# Schema_Circuit_PIA.net
KiCad netlist of a schematic drawn in EasyEDA Pro
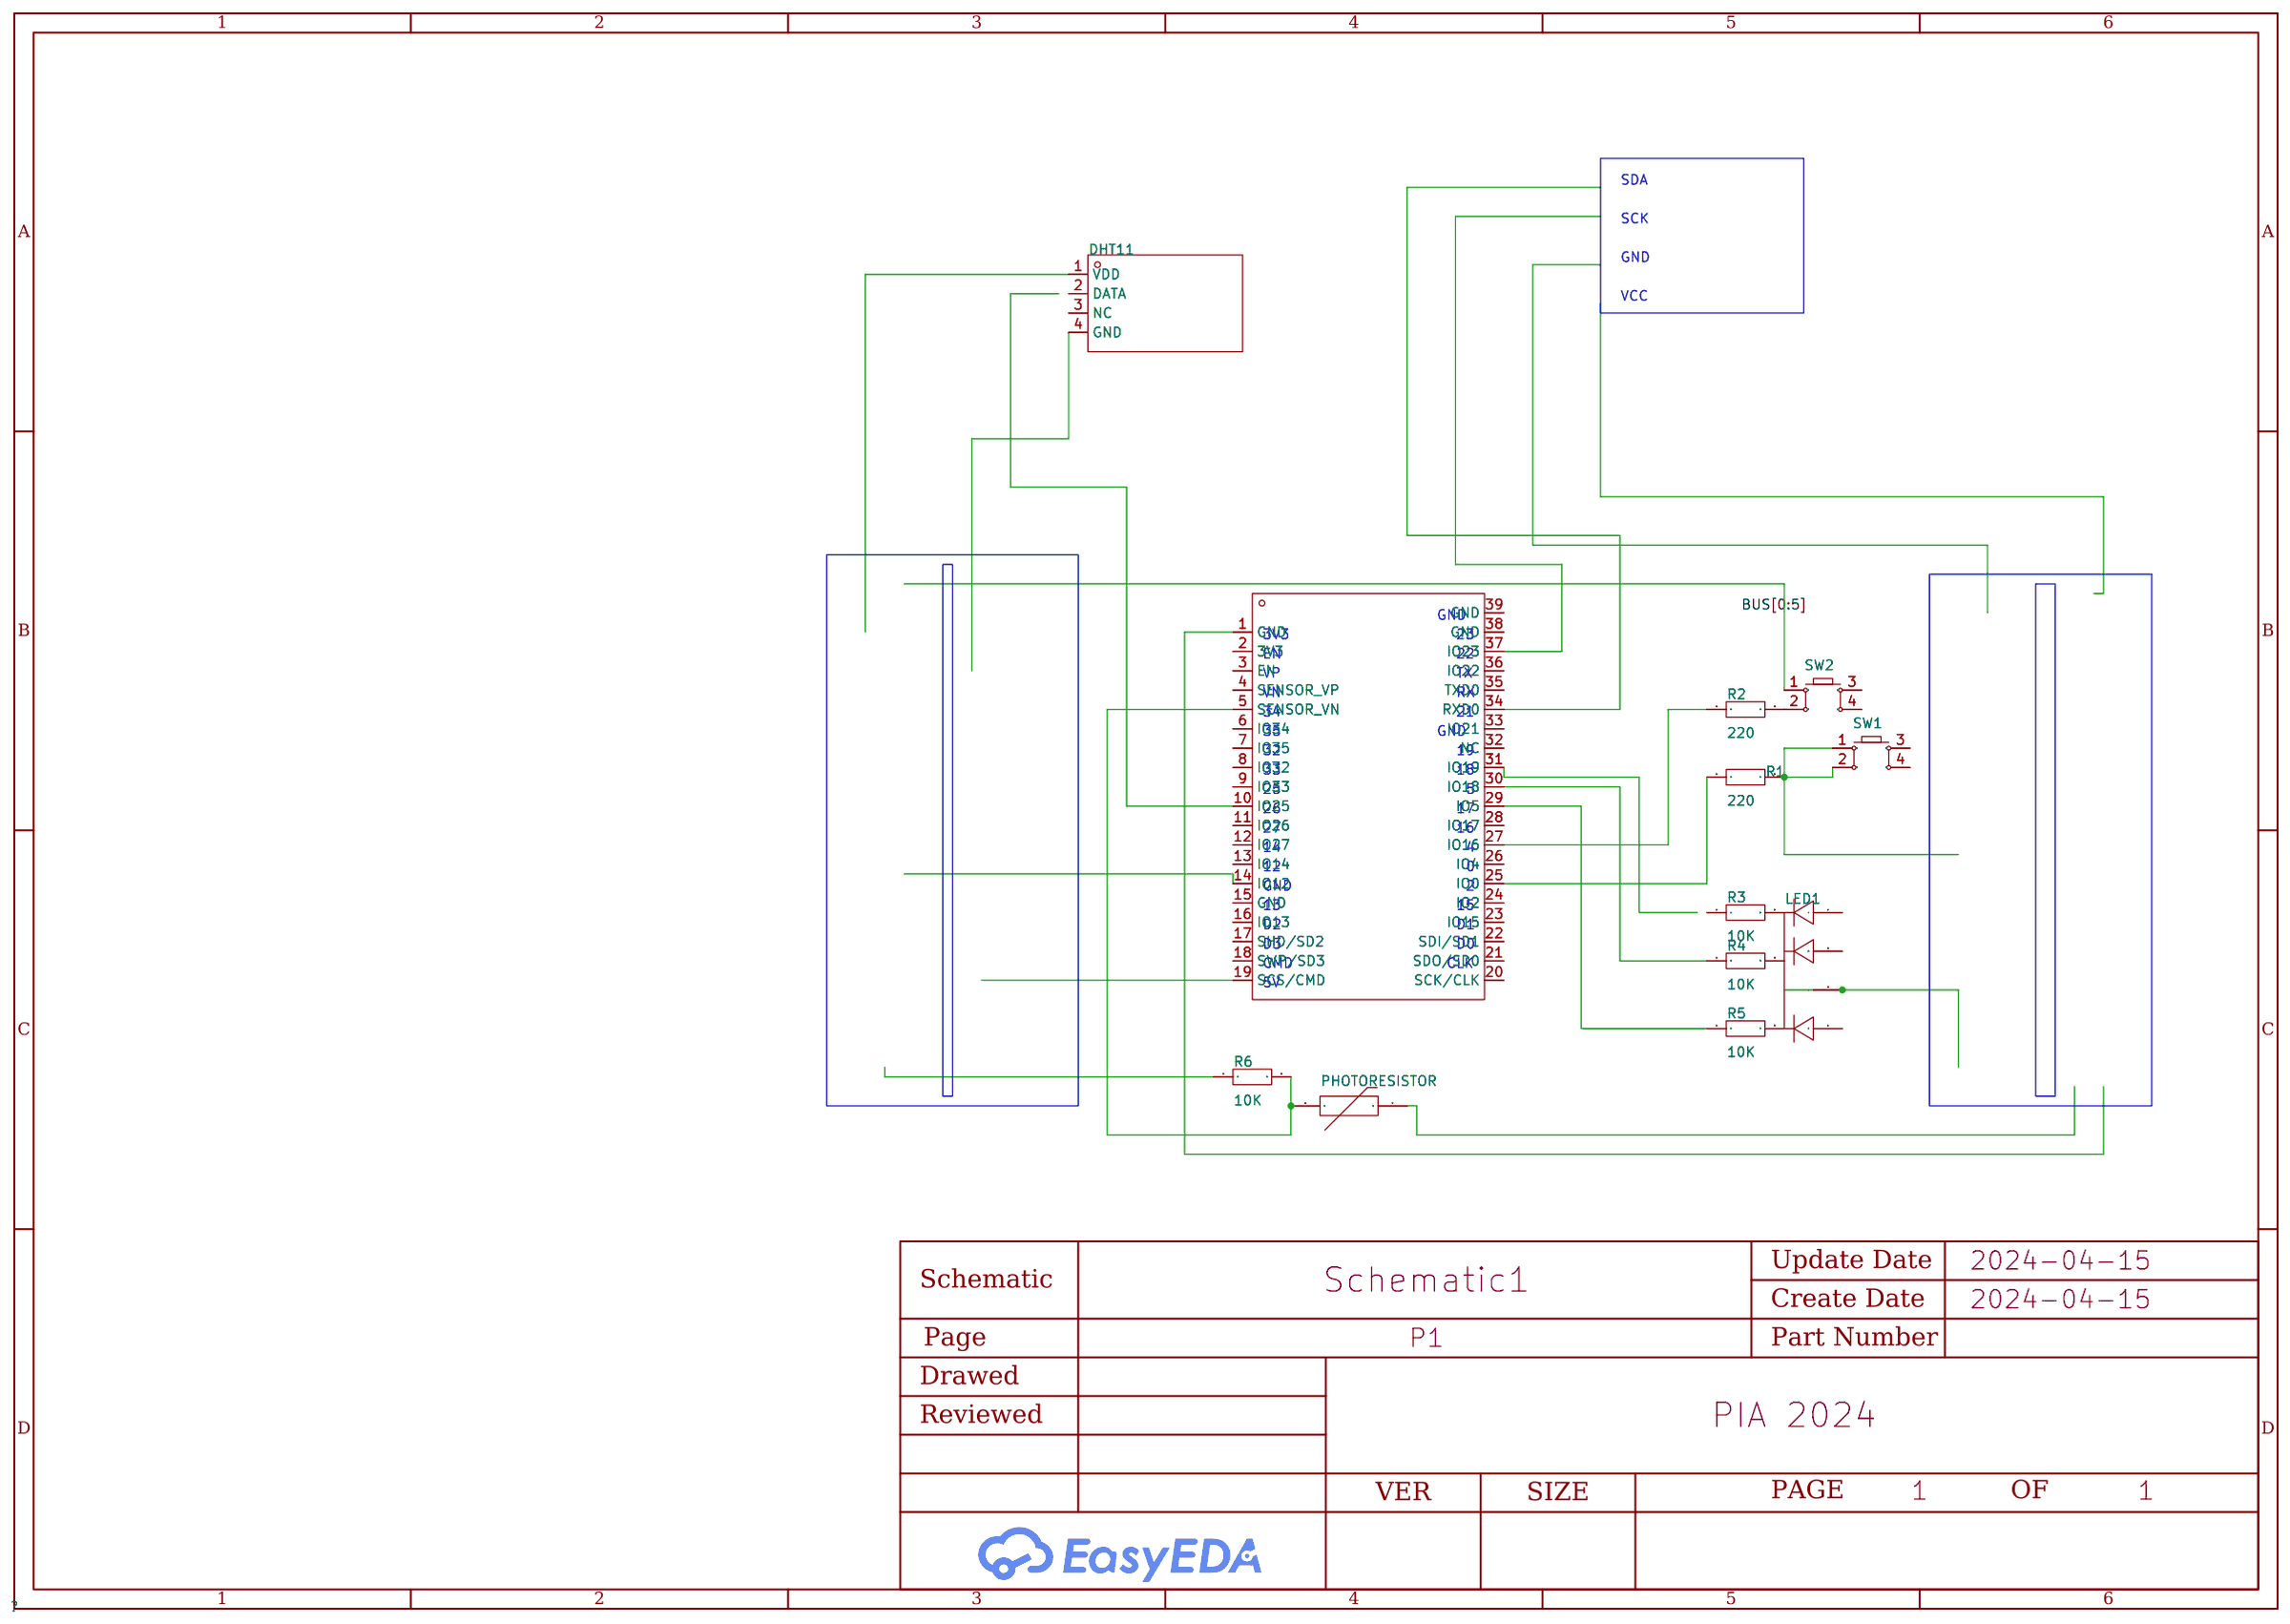
[diagram p0: schematic sheet]

(export (version "E")
  (design (tool "Eeschema 10.0.6"))
  (components
    (comp (ref "DHT11")
      (value "~")
      (footprint "easyedapro:SENSOR-TH_DHT11")
      (fields (field (name "Manufacturer Part") "DHT11") (field (name "Manufacturer") "广州奥松"))
      (libsource (lib "easyedapro") (part "DHT11"))
    )
    (comp (ref "LED1")
      (value "~")
      (footprint "easyedapro:LED-TH_4P-BD5.8-P1.30")
      (description "Emitted Color:RGB")
      (fields
        (field (name "Manufacturer Part") "TJ-L5FYTXHMCSLCRGB-A5")
        (field (name "Manufacturer") "TOGIALED(台湾统佳)")
      )
      (libsource (lib "easyedapro") (part "TJ-L5FYTXHMCSLCRGB-A5"))
    )
    (comp (ref "PHOTORESISTOR")
      (value "~")
      (footprint "easyedapro:RES-TH_L17.5-W6.0-P7.50-D0.8-S5.20")
      (fields (field (name "Manufacturer Part") "MF72 5D15") (field (name "Manufacturer") "时恒"))
      (libsource (lib "easyedapro") (part "MF72-5D15"))
    )
    (comp (ref "R1") (value "220") (footprint "easyedapro:R0603") (libsource (lib "easyedapro") (part "电阻")))
    (comp (ref "R2") (value "220") (footprint "easyedapro:R0603") (libsource (lib "easyedapro") (part "电阻")))
    (comp (ref "R3") (value "10K") (footprint "easyedapro:R0603") (libsource (lib "easyedapro") (part "电阻")))
    (comp (ref "R4") (value "10K") (footprint "easyedapro:R0603") (libsource (lib "easyedapro") (part "电阻")))
    (comp (ref "R5") (value "10K") (footprint "easyedapro:R0603") (libsource (lib "easyedapro") (part "电阻")))
    (comp (ref "R6") (value "10K") (footprint "easyedapro:R0603") (libsource (lib "easyedapro") (part "电阻")))
    (comp (ref "SW1")
      (value "~")
      (footprint "easyedapro:KEY-TH_4P-L6.0-W6.0-P3.90-LS6.5")
      (libsource (lib "easyedapro") (part "轻触按键"))
    )
    (comp (ref "SW2")
      (value "~")
      (footprint "easyedapro:KEY-TH_4P-L6.0-W6.0-P3.90-LS6.5")
      (libsource (lib "easyedapro") (part "轻触按键"))
    )
    (comp (ref "U1")
      (value "~")
      (footprint "easyedapro:WIFIM-SMD_ESP-32S")
      (fields
        (field (name "Manufacturer Part") "ESP32-WROOM-32")
        (field (name "Manufacturer") "ESPRESSIF(乐鑫)")
      )
      (libsource (lib "easyedapro") (part "ESP32-WROOM-32"))
    )
  )
  (nets
    (net (code "2") (name "Net-(R1-Pad2)") (class "Default")
      (node (ref "R1") (pin "2") (pinfunction "2_2") (pintype "input"))
      (node (ref "SW1") (pin "1") (pinfunction "1_1") (pintype "input"))
      (node (ref "SW1") (pin "2") (pinfunction "2_2") (pintype "input"))
    )
    (net (code "3") (name "Net-(R2-Pad2)") (class "Default")
      (node (ref "R2") (pin "2") (pinfunction "2_2") (pintype "input"))
      (node (ref "SW2") (pin "2") (pinfunction "2_2") (pintype "input"))
    )
    (net (code "4") (name "Net-(U1-IO0)") (class "Default")
      (node (ref "R1") (pin "1") (pinfunction "1_1") (pintype "input"))
      (node (ref "U1") (pin "25") (pinfunction "IO0_25") (pintype "input"))
    )
    (net (code "5") (name "Net-(U1-IO5)") (class "Default")
      (node (ref "R5") (pin "1") (pinfunction "1_1") (pintype "input"))
      (node (ref "U1") (pin "29") (pinfunction "IO5_29") (pintype "input"))
    )
    (net (code "6") (name "Net-(U1-IO16)") (class "Default")
      (node (ref "R2") (pin "1") (pinfunction "1_1") (pintype "input"))
      (node (ref "U1") (pin "27") (pinfunction "IO16_27") (pintype "input"))
    )
    (net (code "7") (name "Net-(U1-IO18)") (class "Default")
      (node (ref "R4") (pin "1") (pinfunction "1_1") (pintype "input"))
      (node (ref "U1") (pin "30") (pinfunction "IO18_30") (pintype "input"))
    )
    (net (code "8") (name "Net-(U1-SENSOR_VN)") (class "Default")
      (node (ref "PHOTORESISTOR") (pin "2") (pinfunction "2_2") (pintype "input"))
      (node (ref "R6") (pin "2") (pinfunction "2_2") (pintype "input"))
      (node (ref "U1") (pin "5") (pinfunction "SENSOR_VN_5") (pintype "input"))
    )
    (net (code "9") (name "unconnected-(DHT11-DATA-Pad2)") (class "Default")
      (node (ref "DHT11") (pin "2") (pinfunction "DATA_2") (pintype "input"))
    )
    (net (code "10") (name "unconnected-(DHT11-GND-Pad4)") (class "Default")
      (node (ref "DHT11") (pin "4") (pinfunction "GND_4") (pintype "input"))
    )
    (net (code "11") (name "unconnected-(DHT11-NC-Pad3)") (class "Default")
      (node (ref "DHT11") (pin "3") (pinfunction "NC_3") (pintype "input"))
    )
    (net (code "12") (name "unconnected-(DHT11-VDD-Pad1)") (class "Default")
      (node (ref "DHT11") (pin "1") (pinfunction "VDD_1") (pintype "input"))
    )
    (net (code "13") (name "unconnected-(LED1---Pad2)") (class "Default")
      (node (ref "LED1") (pin "2") (pinfunction "-_2") (pintype "input"))
    )
    (net (code "14") (name "unconnected-(LED1-Pad1)") (class "Default")
      (node (ref "LED1") (pin "1") (pinfunction "1_1") (pintype "input"))
    )
    (net (code "15") (name "unconnected-(LED1-Pad3)") (class "Default")
      (node (ref "LED1") (pin "3") (pinfunction "3_3") (pintype "input"))
    )
    (net (code "16") (name "unconnected-(LED1-Pad4)") (class "Default")
      (node (ref "LED1") (pin "4") (pinfunction "4_4") (pintype "input"))
    )
    (net (code "17") (name "unconnected-(PHOTORESISTOR-Pad1)") (class "Default")
      (node (ref "PHOTORESISTOR") (pin "1") (pinfunction "1_1") (pintype "input"))
    )
    (net (code "18") (name "unconnected-(R3-Pad1)") (class "Default")
      (node (ref "R3") (pin "1") (pinfunction "1_1") (pintype "input"))
    )
    (net (code "19") (name "unconnected-(R3-Pad2)") (class "Default")
      (node (ref "R3") (pin "2") (pinfunction "2_2") (pintype "input"))
    )
    (net (code "20") (name "unconnected-(R4-Pad2)") (class "Default")
      (node (ref "R4") (pin "2") (pinfunction "2_2") (pintype "input"))
    )
    (net (code "21") (name "unconnected-(R5-Pad2)") (class "Default")
      (node (ref "R5") (pin "2") (pinfunction "2_2") (pintype "input"))
    )
    (net (code "22") (name "unconnected-(R6-Pad1)") (class "Default")
      (node (ref "R6") (pin "1") (pinfunction "1_1") (pintype "input"))
    )
    (net (code "23") (name "unconnected-(SW1-Pad3)") (class "Default")
      (node (ref "SW1") (pin "3") (pinfunction "3_3") (pintype "input"))
    )
    (net (code "24") (name "unconnected-(SW1-Pad4)") (class "Default")
      (node (ref "SW1") (pin "4") (pinfunction "4_4") (pintype "input"))
    )
    (net (code "25") (name "unconnected-(SW2-Pad1)") (class "Default")
      (node (ref "SW2") (pin "1") (pinfunction "1_1") (pintype "input"))
    )
    (net (code "26") (name "unconnected-(SW2-Pad3)") (class "Default")
      (node (ref "SW2") (pin "3") (pinfunction "3_3") (pintype "input"))
    )
    (net (code "27") (name "unconnected-(SW2-Pad4)") (class "Default")
      (node (ref "SW2") (pin "4") (pinfunction "4_4") (pintype "input"))
    )
    (net (code "28") (name "unconnected-(U1-3V3-Pad2)") (class "Default")
      (node (ref "U1") (pin "2") (pinfunction "3V3_2") (pintype "input"))
    )
    (net (code "29") (name "unconnected-(U1-EN-Pad3)") (class "Default")
      (node (ref "U1") (pin "3") (pinfunction "EN_3") (pintype "input"))
    )
    (net (code "30") (name "unconnected-(U1-GND-Pad1)") (class "Default")
      (node (ref "U1") (pin "1") (pinfunction "GND_1") (pintype "input"))
    )
    (net (code "31") (name "unconnected-(U1-GND-Pad15)") (class "Default")
      (node (ref "U1") (pin "15") (pinfunction "GND_15") (pintype "input"))
    )
    (net (code "32") (name "unconnected-(U1-GND-Pad38)") (class "Default")
      (node (ref "U1") (pin "38") (pinfunction "GND_38") (pintype "input"))
    )
    (net (code "33") (name "unconnected-(U1-GND-Pad39)") (class "Default")
      (node (ref "U1") (pin "39") (pinfunction "GND_39") (pintype "input"))
    )
    (net (code "34") (name "unconnected-(U1-IO2-Pad24)") (class "Default")
      (node (ref "U1") (pin "24") (pinfunction "IO2_24") (pintype "input"))
    )
    (net (code "35") (name "unconnected-(U1-IO4-Pad26)") (class "Default")
      (node (ref "U1") (pin "26") (pinfunction "IO4_26") (pintype "input"))
    )
    (net (code "36") (name "unconnected-(U1-IO12-Pad14)") (class "Default")
      (node (ref "U1") (pin "14") (pinfunction "IO12_14") (pintype "input"))
    )
    (net (code "37") (name "unconnected-(U1-IO13-Pad16)") (class "Default")
      (node (ref "U1") (pin "16") (pinfunction "IO13_16") (pintype "input"))
    )
    (net (code "38") (name "unconnected-(U1-IO14-Pad13)") (class "Default")
      (node (ref "U1") (pin "13") (pinfunction "IO14_13") (pintype "input"))
    )
    (net (code "39") (name "unconnected-(U1-IO15-Pad23)") (class "Default")
      (node (ref "U1") (pin "23") (pinfunction "IO15_23") (pintype "input"))
    )
    (net (code "40") (name "unconnected-(U1-IO17-Pad28)") (class "Default")
      (node (ref "U1") (pin "28") (pinfunction "IO17_28") (pintype "input"))
    )
    (net (code "41") (name "unconnected-(U1-IO19-Pad31)") (class "Default")
      (node (ref "U1") (pin "31") (pinfunction "IO19_31") (pintype "input"))
    )
    (net (code "42") (name "unconnected-(U1-IO21-Pad33)") (class "Default")
      (node (ref "U1") (pin "33") (pinfunction "IO21_33") (pintype "input"))
    )
    (net (code "43") (name "unconnected-(U1-IO22-Pad36)") (class "Default")
      (node (ref "U1") (pin "36") (pinfunction "IO22_36") (pintype "input"))
    )
    (net (code "44") (name "unconnected-(U1-IO23-Pad37)") (class "Default")
      (node (ref "U1") (pin "37") (pinfunction "IO23_37") (pintype "input"))
    )
    (net (code "45") (name "unconnected-(U1-IO25-Pad10)") (class "Default")
      (node (ref "U1") (pin "10") (pinfunction "IO25_10") (pintype "input"))
    )
    (net (code "46") (name "unconnected-(U1-IO26-Pad11)") (class "Default")
      (node (ref "U1") (pin "11") (pinfunction "IO26_11") (pintype "input"))
    )
    (net (code "47") (name "unconnected-(U1-IO27-Pad12)") (class "Default")
      (node (ref "U1") (pin "12") (pinfunction "IO27_12") (pintype "input"))
    )
    (net (code "48") (name "unconnected-(U1-IO32-Pad8)") (class "Default")
      (node (ref "U1") (pin "8") (pinfunction "IO32_8") (pintype "input"))
    )
    (net (code "49") (name "unconnected-(U1-IO33-Pad9)") (class "Default")
      (node (ref "U1") (pin "9") (pinfunction "IO33_9") (pintype "input"))
    )
    (net (code "50") (name "unconnected-(U1-IO34-Pad6)") (class "Default")
      (node (ref "U1") (pin "6") (pinfunction "IO34_6") (pintype "input"))
    )
    (net (code "51") (name "unconnected-(U1-IO35-Pad7)") (class "Default")
      (node (ref "U1") (pin "7") (pinfunction "IO35_7") (pintype "input"))
    )
    (net (code "52") (name "unconnected-(U1-NC-Pad32)") (class "Default")
      (node (ref "U1") (pin "32") (pinfunction "NC_32") (pintype "input"))
    )
    (net (code "53") (name "unconnected-(U1-RXD0-Pad34)") (class "Default")
      (node (ref "U1") (pin "34") (pinfunction "RXD0_34") (pintype "input"))
    )
    (net (code "54") (name "unconnected-(U1-SCK{slash}CLK-Pad20)") (class "Default")
      (node (ref "U1") (pin "20") (pinfunction "SCK/CLK_20") (pintype "input"))
    )
    (net (code "55") (name "unconnected-(U1-SCS{slash}CMD-Pad19)") (class "Default")
      (node (ref "U1") (pin "19") (pinfunction "SCS/CMD_19") (pintype "input"))
    )
    (net (code "56") (name "unconnected-(U1-SDI{slash}SD1-Pad22)") (class "Default")
      (node (ref "U1") (pin "22") (pinfunction "SDI/SD1_22") (pintype "input"))
    )
    (net (code "57") (name "unconnected-(U1-SDO{slash}SD0-Pad21)") (class "Default")
      (node (ref "U1") (pin "21") (pinfunction "SDO/SD0_21") (pintype "input"))
    )
    (net (code "58") (name "unconnected-(U1-SENSOR_VP-Pad4)") (class "Default")
      (node (ref "U1") (pin "4") (pinfunction "SENSOR_VP_4") (pintype "input"))
    )
    (net (code "59") (name "unconnected-(U1-SHD{slash}SD2-Pad17)") (class "Default")
      (node (ref "U1") (pin "17") (pinfunction "SHD/SD2_17") (pintype "input"))
    )
    (net (code "60") (name "unconnected-(U1-SWP{slash}SD3-Pad18)") (class "Default")
      (node (ref "U1") (pin "18") (pinfunction "SWP/SD3_18") (pintype "input"))
    )
    (net (code "61") (name "unconnected-(U1-TXD0-Pad35)") (class "Default")
      (node (ref "U1") (pin "35") (pinfunction "TXD0_35") (pintype "input"))
    )
  )
)
